# DCDC_5V.net
KiCad netlist of a schematic drawn in Altium Designer
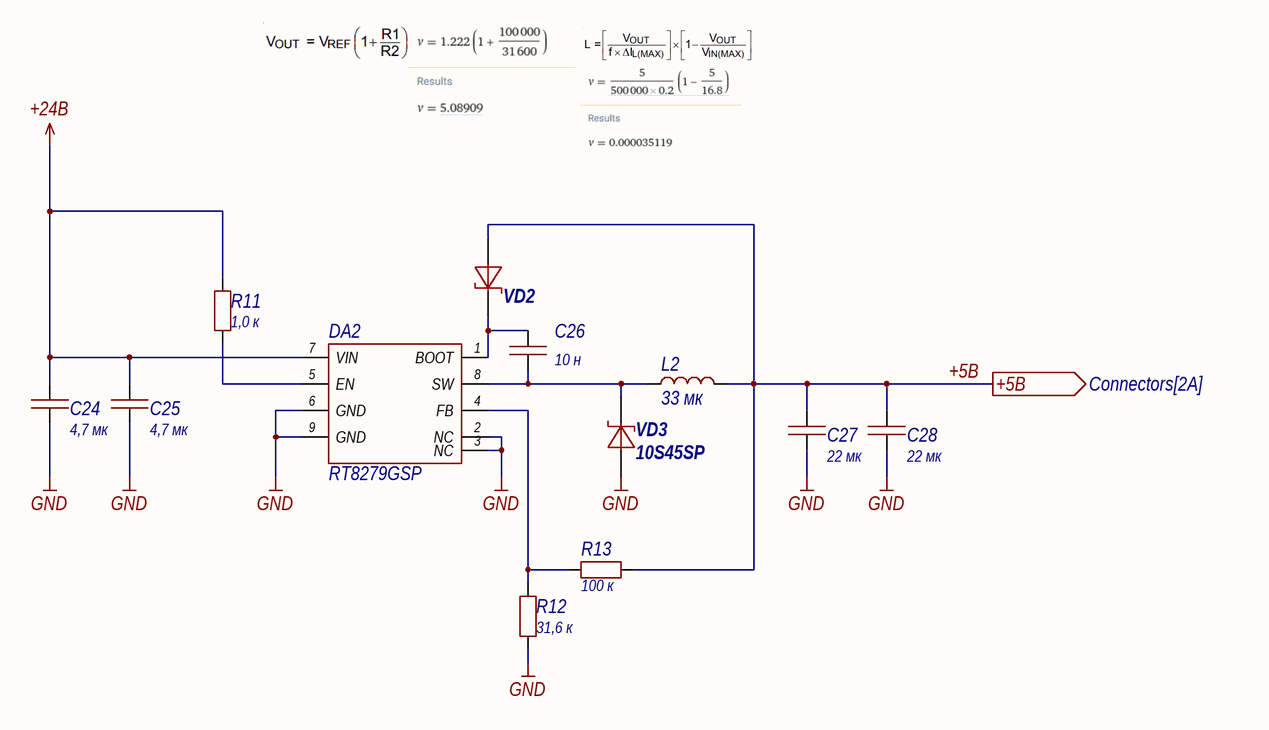
[diagram p0: DCDC_5V.SchDoc]

(export (version "E")
  (design (tool "Eeschema 10.0.6"))
  (components
    (comp (ref "C24")
      (value "4,7 мк")
      (footprint "1206C")
      (description "Конденсатор")
      (fields (field (name "PART NUMBER") "Capacitor_4,7u_10_50V_X7R_1206C") (field (name "TOLERANCE") "0,1"))
      (libsource (lib "Hydrolib") (part "Capacitor"))
    )
    (comp (ref "C25")
      (value "4,7 мк")
      (footprint "1206C")
      (description "Конденсатор")
      (fields (field (name "PART NUMBER") "Capacitor_4,7u_10_50V_X7R_1206C") (field (name "TOLERANCE") "0,1"))
      (libsource (lib "Hydrolib") (part "Capacitor"))
    )
    (comp (ref "C26")
      (value "10 н")
      (footprint "0603C")
      (description "Конденсатор")
      (fields (field (name "PART NUMBER") "Capacitor_10n_10_50V_X7R_0603C") (field (name "TOLERANCE") "0,1"))
      (libsource (lib "Hydrolib") (part "Capacitor"))
    )
    (comp (ref "C27")
      (value "22 мк")
      (footprint "1210C")
      (description "Конденсатор")
      (fields (field (name "PART NUMBER") "Capacitor_22u_10_25V_X7R_1210C") (field (name "TOLERANCE") "0,1"))
      (libsource (lib "Hydrolib") (part "Capacitor"))
    )
    (comp (ref "C28")
      (value "22 мк")
      (footprint "1210C")
      (description "Конденсатор")
      (fields (field (name "PART NUMBER") "Capacitor_22u_10_25V_X7R_1210C") (field (name "TOLERANCE") "0,1"))
      (libsource (lib "Hydrolib") (part "Capacitor"))
    )
    (comp (ref "DA2")
      (value "RT8279GSP")
      (footprint "8SOP(Exposed_Pad)")
      (description "Преобразователь постоянного тока понижающий подстраиваемый выход 5А")
      (libsource (lib "Hydrolib") (part "RT8279GSP"))
    )
    (comp (ref "L2")
      (value "33 мк")
      (footprint "IHLP-4040")
      (description "ЧИП-индуктивность экранированная 33мкГн ±20% 4,4A 94,5мОм 4040")
      (fields (field (name "PART NUMBER") "IHLP4040DZER330M11"))
      (libsource (lib "Hydrolib") (part "Inductance"))
    )
    (comp (ref "R11")
      (value "1,0 к")
      (footprint "0603R")
      (description "Резистор номиналом 1,0 кОм и точностью 1%")
      (fields (field (name "PART NUMBER") "Resistor_1.0k_1_0603") (field (name "TOLERANCE") "1%"))
      (libsource (lib "Hydrolib") (part "Resistor"))
    )
    (comp (ref "R12")
      (value "31,6 к")
      (footprint "0603R")
      (description "Резистор номиналом 31,6 кОм и точностью 1%")
      (fields (field (name "PART NUMBER") "Resistor_31.6k_1_0603") (field (name "TOLERANCE") "1%"))
      (libsource (lib "Hydrolib") (part "Resistor"))
    )
    (comp (ref "R13")
      (value "100 к")
      (footprint "0603R")
      (description "Резистор номиналом 100 кОм и точностью 1%")
      (fields (field (name "PART NUMBER") "Resistor_100k_1_0603") (field (name "TOLERANCE") "1%"))
      (libsource (lib "") (part "Resistor_1"))
    )
    (comp (ref "VD2")
      (value "BAT54WS")
      (footprint "SOD-323")
      (description "Диод шоттки на 30 В, ном. ток 0.2 А")
      (libsource (lib "Hydrolib") (part "Schottky_diode"))
    )
    (comp (ref "VD3")
      (value "10S45SP")
      (footprint "TO-277")
      (description "Диод шоттки на 45 В, ном. ток 10 А")
      (libsource (lib "Hydrolib") (part "Schottky_diode"))
    )
  )
  (nets
    (net (code "1") (name "+24В") (class "Default")
      (node (ref "C24") (pin "2") (pinfunction "2_2") (pintype "passive"))
      (node (ref "C25") (pin "2") (pinfunction "2_2") (pintype "passive"))
      (node (ref "DA2") (pin "7") (pinfunction "VIN_7") (pintype "passive"))
      (node (ref "R11") (pin "2") (pinfunction "2_2") (pintype "passive"))
    )
    (net (code "2") (name "/+5В") (class "Default")
      (node (ref "C27") (pin "2") (pinfunction "2_2") (pintype "passive"))
      (node (ref "C28") (pin "2") (pinfunction "2_2") (pintype "passive"))
      (node (ref "L2") (pin "2") (pinfunction "2_2") (pintype "passive"))
      (node (ref "R13") (pin "2") (pinfunction "2_2") (pintype "passive"))
      (node (ref "VD2") (pin "1") (pinfunction "1_1") (pintype "passive"))
    )
    (net (code "3") (name "GND") (class "Default")
      (node (ref "C24") (pin "1") (pinfunction "1_1") (pintype "passive"))
      (node (ref "C25") (pin "1") (pinfunction "1_1") (pintype "passive"))
      (node (ref "C27") (pin "1") (pinfunction "1_1") (pintype "passive"))
      (node (ref "C28") (pin "1") (pinfunction "1_1") (pintype "passive"))
      (node (ref "DA2") (pin "2") (pinfunction "NC_2") (pintype "passive"))
      (node (ref "DA2") (pin "3") (pinfunction "NC_3") (pintype "passive"))
      (node (ref "DA2") (pin "6") (pinfunction "GND_6") (pintype "passive"))
      (node (ref "DA2") (pin "9") (pinfunction "GND_9") (pintype "passive"))
      (node (ref "R12") (pin "1") (pinfunction "1_1") (pintype "passive"))
      (node (ref "VD3") (pin "1") (pinfunction "1_1") (pintype "passive"))
    )
    (net (code "4") (name "Net-(DA2-BOOT)") (class "Default")
      (node (ref "C26") (pin "2") (pinfunction "2_2") (pintype "passive"))
      (node (ref "DA2") (pin "1") (pinfunction "BOOT_1") (pintype "passive"))
      (node (ref "VD2") (pin "2") (pinfunction "2_2") (pintype "passive"))
    )
    (net (code "5") (name "Net-(DA2-EN)") (class "Default")
      (node (ref "DA2") (pin "5") (pinfunction "EN_5") (pintype "passive"))
      (node (ref "R11") (pin "1") (pinfunction "1_1") (pintype "passive"))
    )
    (net (code "6") (name "Net-(DA2-FB)") (class "Default")
      (node (ref "DA2") (pin "4") (pinfunction "FB_4") (pintype "passive"))
      (node (ref "R12") (pin "2") (pinfunction "2_2") (pintype "passive"))
      (node (ref "R13") (pin "1") (pinfunction "1_1") (pintype "passive"))
    )
    (net (code "7") (name "Net-(DA2-SW)") (class "Default")
      (node (ref "C26") (pin "1") (pinfunction "1_1") (pintype "passive"))
      (node (ref "DA2") (pin "8") (pinfunction "SW_8") (pintype "passive"))
      (node (ref "L2") (pin "1") (pinfunction "1_1") (pintype "passive"))
      (node (ref "VD3") (pin "2") (pinfunction "2_2") (pintype "passive"))
    )
  )
)
